# MotherBoard_rev1.net
KiCad netlist of a schematic drawn in EAGLE
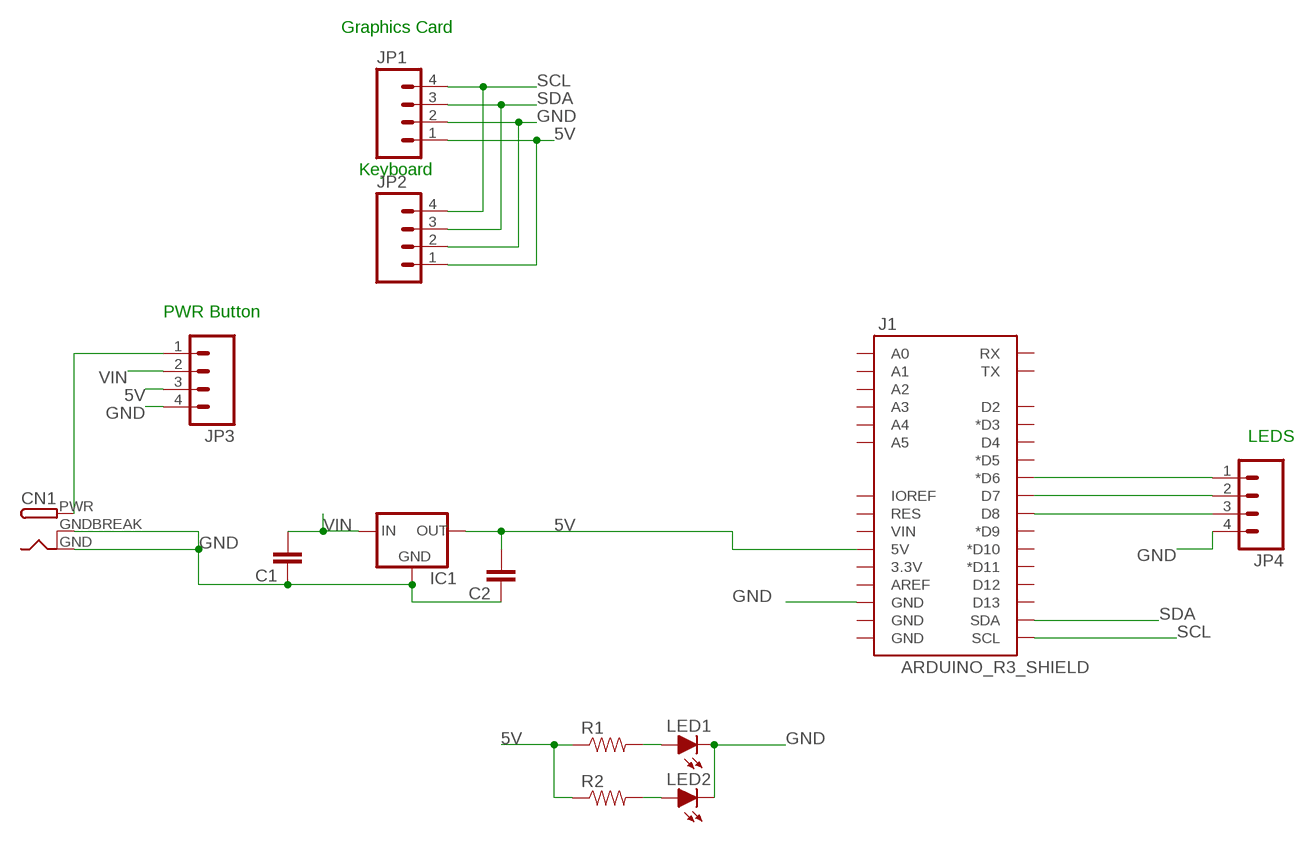
[diagram p0: schematic, sheet 1]

(export (version "E")
  (design (tool "Eeschema 10.0.6"))
  (components
    (comp (ref "C1")
      (value "CAPPTH3")
      (footprint "eagle-import:CAP-PTH-LARGE")
      (libsource (lib "eagle-import") (part "CAPPTH3"))
    )
    (comp (ref "C2")
      (value "CAPPTH3")
      (footprint "eagle-import:CAP-PTH-LARGE")
      (libsource (lib "eagle-import") (part "CAPPTH3"))
    )
    (comp (ref "CN1")
      (value "DCBARRELPTH")
      (footprint "eagle-import:DCJACK_2MM_PTH")
      (libsource (lib "eagle-import") (part "DCBARRELPTH"))
    )
    (comp (ref "IC1")
      (value "5VREG_L7805SPACED")
      (footprint "eagle-import:TO-220-SPACED")
      (libsource (lib "eagle-import") (part "5VREG_L7805SPACED"))
    )
    (comp (ref "J1")
      (value "ARDUINO_R3_SHIELD")
      (footprint "eagle-import:UNO_R3_SHIELD")
      (libsource (lib "eagle-import") (part "ARDUINO_R3_SHIELD"))
    )
    (comp (ref "JP1")
      (value "M04")
      (footprint "eagle-import:1X04")
      (libsource (lib "eagle-import") (part "M04"))
    )
    (comp (ref "JP2")
      (value "M04")
      (footprint "eagle-import:1X04")
      (libsource (lib "eagle-import") (part "M04"))
    )
    (comp (ref "JP3")
      (value "M04")
      (footprint "eagle-import:1X04")
      (libsource (lib "eagle-import") (part "M04"))
    )
    (comp (ref "JP4")
      (value "M04")
      (footprint "eagle-import:1X04")
      (libsource (lib "eagle-import") (part "M04"))
    )
    (comp (ref "LED1")
      (value "LED-5MM")
      (footprint "eagle-import:LED-5MM")
      (libsource (lib "eagle-import") (part "LED-5MM"))
    )
    (comp (ref "LED2")
      (value "LED-5MM")
      (footprint "eagle-import:LED-5MM")
      (libsource (lib "eagle-import") (part "LED-5MM"))
    )
    (comp (ref "R1")
      (value "RESISTORPTH-1/2W")
      (footprint "eagle-import:AXIAL-0.5")
      (libsource (lib "eagle-import") (part "RESISTORPTH-1/2W"))
    )
    (comp (ref "R2")
      (value "RESISTORPTH-1/2W")
      (footprint "eagle-import:AXIAL-0.5")
      (libsource (lib "eagle-import") (part "RESISTORPTH-1/2W"))
    )
  )
  (nets
    (net (code "1") (name "/5V") (class "Default")
      (node (ref "C2") (pin "2") (pinfunction "2_2") (pintype "passive"))
      (node (ref "IC1") (pin "3") (pinfunction "OUT_3") (pintype "output"))
      (node (ref "J1") (pin "5V") (pinfunction "5V_5V") (pintype "bidirectional"))
      (node (ref "JP1") (pin "1") (pinfunction "1_1") (pintype "passive"))
      (node (ref "JP2") (pin "1") (pinfunction "1_1") (pintype "passive"))
      (node (ref "JP3") (pin "3") (pinfunction "3_3") (pintype "passive"))
      (node (ref "R1") (pin "P$1") (pinfunction "1_P$1") (pintype "passive"))
      (node (ref "R2") (pin "P$1") (pinfunction "1_P$1") (pintype "passive"))
    )
    (net (code "2") (name "/GND") (class "Default")
      (node (ref "C1") (pin "1") (pinfunction "1_1") (pintype "passive"))
      (node (ref "C2") (pin "1") (pinfunction "1_1") (pintype "passive"))
      (node (ref "CN1") (pin "GND") (pinfunction "GND_GND") (pintype "power_in"))
      (node (ref "CN1") (pin "GNDBREAK") (pinfunction "GNDBREAK_GNDBREAK") (pintype "power_in"))
      (node (ref "IC1") (pin "2") (pinfunction "GND_2") (pintype "input"))
      (node (ref "J1") (pin "GND@2") (pinfunction "GND_GND@2") (pintype "bidirectional"))
      (node (ref "JP1") (pin "2") (pinfunction "2_2") (pintype "passive"))
      (node (ref "JP2") (pin "2") (pinfunction "2_2") (pintype "passive"))
      (node (ref "JP3") (pin "4") (pinfunction "4_4") (pintype "passive"))
      (node (ref "JP4") (pin "4") (pinfunction "4_4") (pintype "passive"))
      (node (ref "LED1") (pin "K") (pinfunction "C_K") (pintype "passive"))
      (node (ref "LED2") (pin "K") (pinfunction "C_K") (pintype "passive"))
    )
    (net (code "3") (name "/SCL") (class "Default")
      (node (ref "J1") (pin "SCL") (pinfunction "SCL_SCL") (pintype "bidirectional"))
      (node (ref "JP1") (pin "4") (pinfunction "4_4") (pintype "passive"))
      (node (ref "JP2") (pin "4") (pinfunction "4_4") (pintype "passive"))
    )
    (net (code "4") (name "/SDA") (class "Default")
      (node (ref "J1") (pin "SDA") (pinfunction "SDA_SDA") (pintype "bidirectional"))
      (node (ref "JP1") (pin "3") (pinfunction "3_3") (pintype "passive"))
      (node (ref "JP2") (pin "3") (pinfunction "3_3") (pintype "passive"))
    )
    (net (code "5") (name "/VIN") (class "Default")
      (node (ref "C1") (pin "2") (pinfunction "2_2") (pintype "passive"))
      (node (ref "IC1") (pin "1") (pinfunction "IN_1") (pintype "input"))
      (node (ref "JP3") (pin "2") (pinfunction "2_2") (pintype "passive"))
    )
    (net (code "6") (name "Net-(CN1-PadPWR)") (class "Default")
      (node (ref "CN1") (pin "PWR") (pinfunction "PWR_PWR") (pintype "power_in"))
      (node (ref "JP3") (pin "1") (pinfunction "1_1") (pintype "passive"))
    )
    (net (code "7") (name "Net-(J1-*D6)") (class "Default")
      (node (ref "J1") (pin "D6") (pinfunction "*D6_D6") (pintype "bidirectional"))
      (node (ref "JP4") (pin "1") (pinfunction "1_1") (pintype "passive"))
    )
    (net (code "8") (name "Net-(J1-PadD7)") (class "Default")
      (node (ref "J1") (pin "D7") (pinfunction "D7_D7") (pintype "bidirectional"))
      (node (ref "JP4") (pin "2") (pinfunction "2_2") (pintype "passive"))
    )
    (net (code "9") (name "Net-(J1-PadD8)") (class "Default")
      (node (ref "J1") (pin "D8") (pinfunction "D8_D8") (pintype "bidirectional"))
      (node (ref "JP4") (pin "3") (pinfunction "3_3") (pintype "passive"))
    )
    (net (code "10") (name "Net-(R1-2)") (class "Default")
      (node (ref "LED1") (pin "A") (pinfunction "A_A") (pintype "passive"))
      (node (ref "R1") (pin "P$2") (pinfunction "2_P$2") (pintype "passive"))
    )
    (net (code "11") (name "Net-(R2-2)") (class "Default")
      (node (ref "LED2") (pin "A") (pinfunction "A_A") (pintype "passive"))
      (node (ref "R2") (pin "P$2") (pinfunction "2_P$2") (pintype "passive"))
    )
    (net (code "12") (name "unconnected-(J1-*D3-PadD3)") (class "Default")
      (node (ref "J1") (pin "D3") (pinfunction "*D3_D3") (pintype "bidirectional"))
    )
    (net (code "13") (name "unconnected-(J1-*D5-PadD5)") (class "Default")
      (node (ref "J1") (pin "D5") (pinfunction "*D5_D5") (pintype "bidirectional"))
    )
    (net (code "14") (name "unconnected-(J1-*D9-PadD9)") (class "Default")
      (node (ref "J1") (pin "D9") (pinfunction "*D9_D9") (pintype "bidirectional"))
    )
    (net (code "15") (name "unconnected-(J1-*D10-PadD10)") (class "Default")
      (node (ref "J1") (pin "D10") (pinfunction "*D10_D10") (pintype "bidirectional"))
    )
    (net (code "16") (name "unconnected-(J1-*D11-PadD11)") (class "Default")
      (node (ref "J1") (pin "D11") (pinfunction "*D11_D11") (pintype "bidirectional"))
    )
    (net (code "17") (name "unconnected-(J1-GND-PadGND@0)") (class "Default")
      (node (ref "J1") (pin "GND@0") (pinfunction "GND_GND@0") (pintype "bidirectional"))
    )
    (net (code "18") (name "unconnected-(J1-GND-PadGND@1)") (class "Default")
      (node (ref "J1") (pin "GND@1") (pinfunction "GND_GND@1") (pintype "bidirectional"))
    )
    (net (code "19") (name "unconnected-(J1-Pad3.3V)") (class "Default")
      (node (ref "J1") (pin "3.3V") (pinfunction "3.3V_3.3V") (pintype "bidirectional"))
    )
    (net (code "20") (name "unconnected-(J1-PadA0)") (class "Default")
      (node (ref "J1") (pin "A0") (pinfunction "A0_A0") (pintype "bidirectional"))
    )
    (net (code "21") (name "unconnected-(J1-PadA1)") (class "Default")
      (node (ref "J1") (pin "A1") (pinfunction "A1_A1") (pintype "bidirectional"))
    )
    (net (code "22") (name "unconnected-(J1-PadA2)") (class "Default")
      (node (ref "J1") (pin "A2") (pinfunction "A2_A2") (pintype "bidirectional"))
    )
    (net (code "23") (name "unconnected-(J1-PadA3)") (class "Default")
      (node (ref "J1") (pin "A3") (pinfunction "A3_A3") (pintype "bidirectional"))
    )
    (net (code "24") (name "unconnected-(J1-PadA4)") (class "Default")
      (node (ref "J1") (pin "A4") (pinfunction "A4_A4") (pintype "bidirectional"))
    )
    (net (code "25") (name "unconnected-(J1-PadA5)") (class "Default")
      (node (ref "J1") (pin "A5") (pinfunction "A5_A5") (pintype "bidirectional"))
    )
    (net (code "26") (name "unconnected-(J1-PadAREF)") (class "Default")
      (node (ref "J1") (pin "AREF") (pinfunction "AREF_AREF") (pintype "bidirectional"))
    )
    (net (code "27") (name "unconnected-(J1-PadD2)") (class "Default")
      (node (ref "J1") (pin "D2") (pinfunction "D2_D2") (pintype "bidirectional"))
    )
    (net (code "28") (name "unconnected-(J1-PadD4)") (class "Default")
      (node (ref "J1") (pin "D4") (pinfunction "D4_D4") (pintype "bidirectional"))
    )
    (net (code "29") (name "unconnected-(J1-PadD12)") (class "Default")
      (node (ref "J1") (pin "D12") (pinfunction "D12_D12") (pintype "bidirectional"))
    )
    (net (code "30") (name "unconnected-(J1-PadD13)") (class "Default")
      (node (ref "J1") (pin "D13") (pinfunction "D13_D13") (pintype "bidirectional"))
    )
    (net (code "31") (name "unconnected-(J1-PadIOREF)") (class "Default")
      (node (ref "J1") (pin "IOREF") (pinfunction "IOREF_IOREF") (pintype "bidirectional"))
    )
    (net (code "32") (name "unconnected-(J1-PadRES)") (class "Default")
      (node (ref "J1") (pin "RES") (pinfunction "RES_RES") (pintype "bidirectional"))
    )
    (net (code "33") (name "unconnected-(J1-PadRX)") (class "Default")
      (node (ref "J1") (pin "RX") (pinfunction "RX_RX") (pintype "bidirectional"))
    )
    (net (code "34") (name "unconnected-(J1-PadTX)") (class "Default")
      (node (ref "J1") (pin "TX") (pinfunction "TX_TX") (pintype "bidirectional"))
    )
    (net (code "35") (name "unconnected-(J1-PadVIN)") (class "Default")
      (node (ref "J1") (pin "VIN") (pinfunction "VIN_VIN") (pintype "bidirectional"))
    )
  )
)
